# MagEnc2.net
KiCad netlist of a schematic drawn in EAGLE
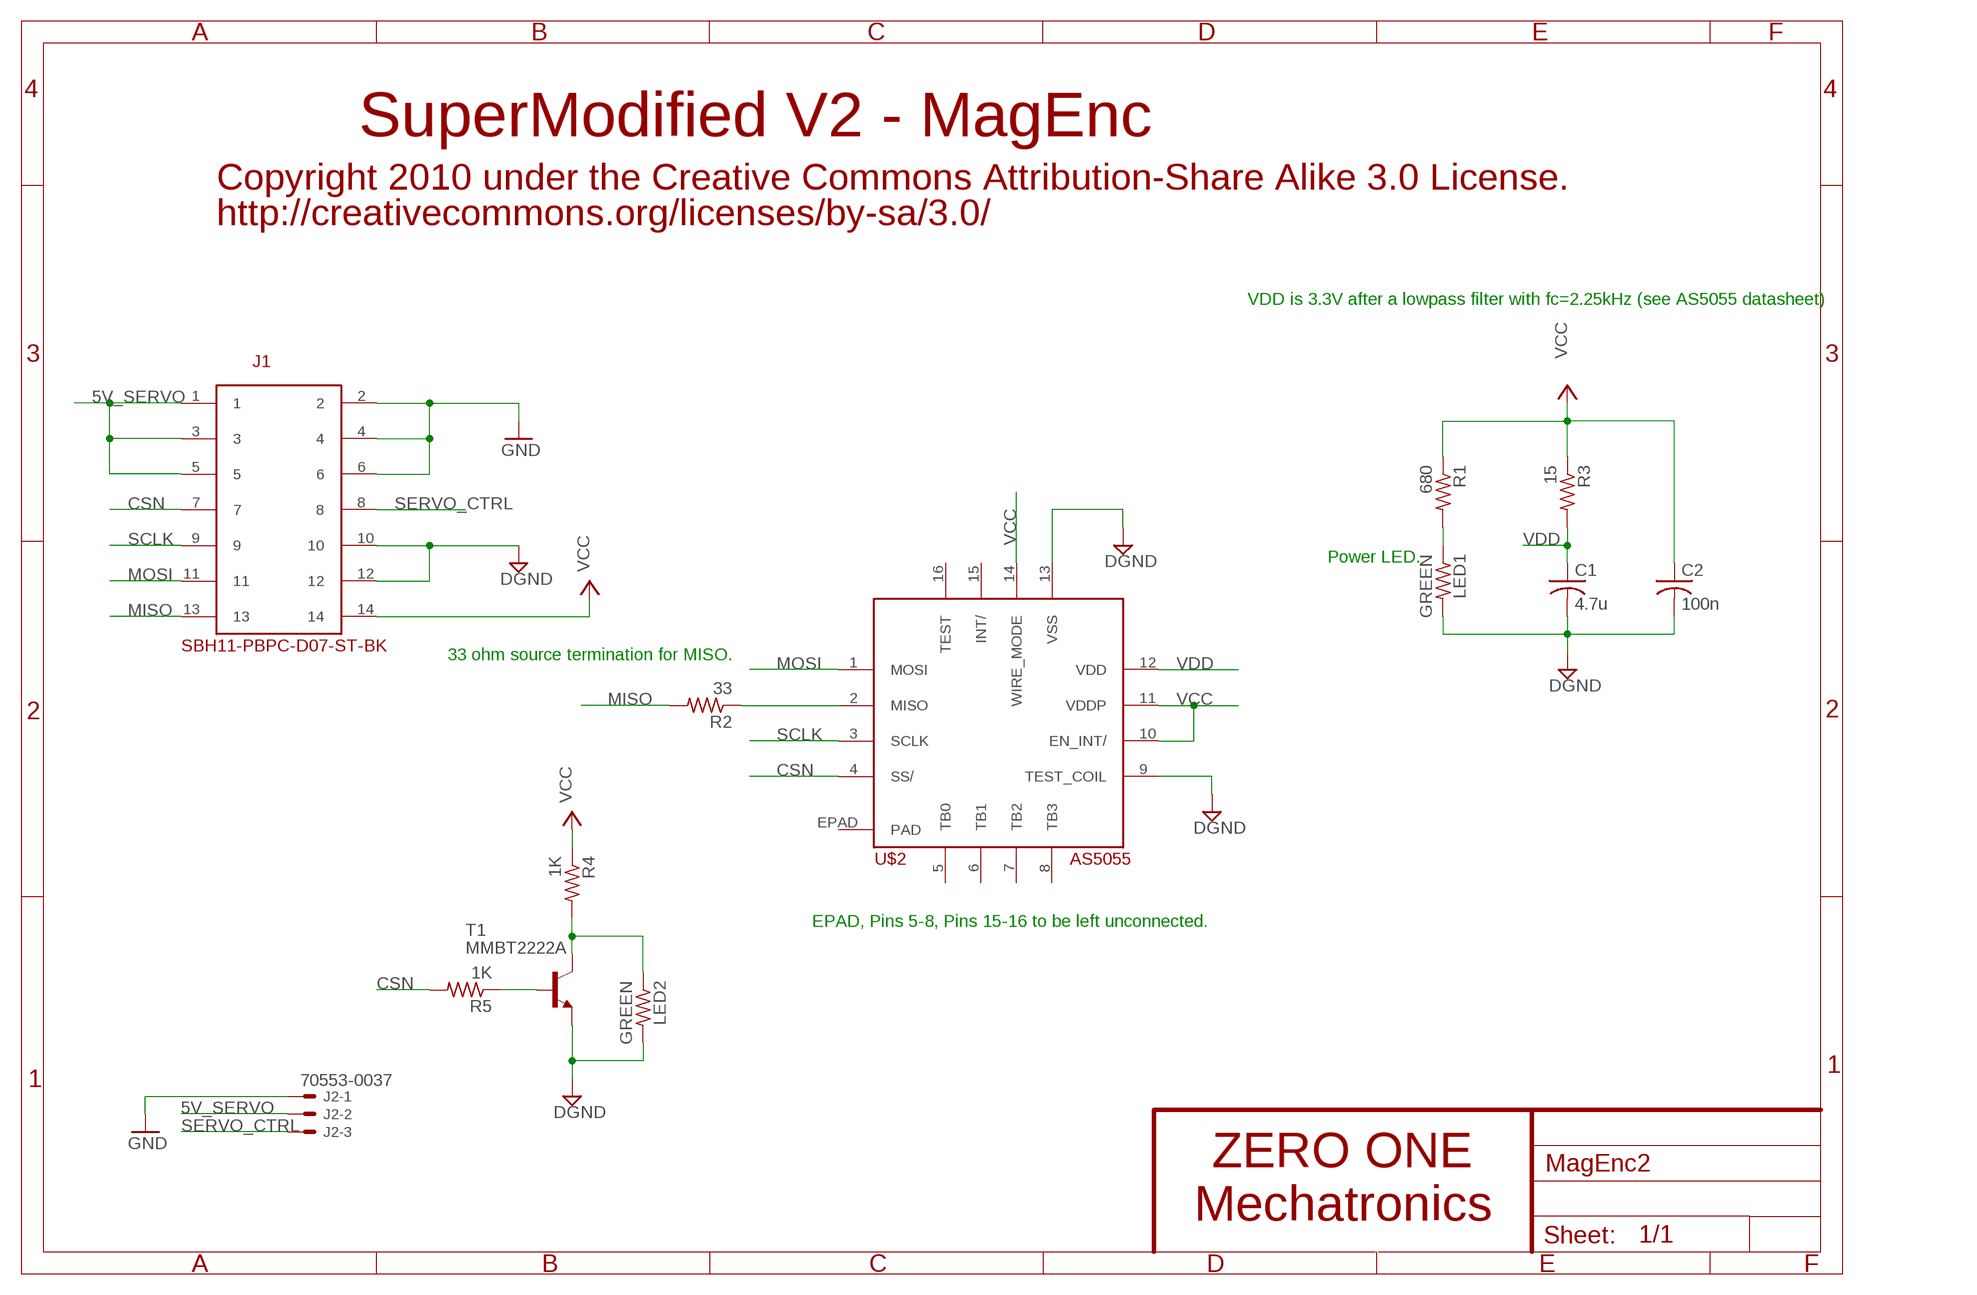
[diagram p0: schematic, sheet 1]

(export (version "E")
  (design (tool "Eeschema 10.0.6"))
  (components
    (comp (ref "C1")
      (value "4.7u")
      (footprint "eagle-import:C0402")
      (libsource (lib "eagle-import") (part "C-USC0402"))
    )
    (comp (ref "C2")
      (value "100n")
      (footprint "eagle-import:C0402")
      (libsource (lib "eagle-import") (part "C-USC0402"))
    )
    (comp (ref "J1")
      (value "SBH11-PBPC-D07-ST-BK")
      (footprint "eagle-import:SBH11-PBPC-D07-ST-BK")
      (libsource (lib "eagle-import") (part "SBH11-PBPC-D07-ST-BK"))
    )
    (comp (ref "J2")
      (value "70553-0037")
      (footprint "eagle-import:70553-03")
      (libsource (lib "eagle-import") (part "C-GRID-03-70553"))
    )
    (comp (ref "LED1")
      (value "GREEN")
      (footprint "eagle-import:R0402")
      (libsource (lib "eagle-import") (part "R-US_R0402"))
    )
    (comp (ref "LED2")
      (value "GREEN")
      (footprint "eagle-import:R0402")
      (libsource (lib "eagle-import") (part "R-US_R0402"))
    )
    (comp (ref "R1")
      (value "680")
      (footprint "eagle-import:R0402")
      (libsource (lib "eagle-import") (part "R-US_R0402"))
    )
    (comp (ref "R2")
      (value "33")
      (footprint "eagle-import:R0402")
      (libsource (lib "eagle-import") (part "R-US_R0402"))
    )
    (comp (ref "R3")
      (value "15")
      (footprint "eagle-import:R0402")
      (libsource (lib "eagle-import") (part "R-US_R0402"))
    )
    (comp (ref "R4")
      (value "1K")
      (footprint "eagle-import:R0402")
      (libsource (lib "eagle-import") (part "R-US_R0402"))
    )
    (comp (ref "R5")
      (value "1K")
      (footprint "eagle-import:R0402")
      (libsource (lib "eagle-import") (part "R-US_R0402"))
    )
    (comp (ref "T1")
      (value "MMBT2222A")
      (footprint "eagle-import:SOT23-BEC")
      (libsource (lib "eagle-import") (part "-NPN-SOT23-BECMMBT2222ALT1"))
    )
    (comp (ref "U$2")
      (value "AS5055")
      (footprint "eagle-import:AS5055")
      (libsource (lib "eagle-import") (part "AS5055"))
    )
  )
  (nets
    (net (code "1") (name "/5V_SERVO") (class "Default")
      (node (ref "J1") (pin "1") (pinfunction "1_1") (pintype "bidirectional"))
      (node (ref "J1") (pin "3") (pinfunction "3_3") (pintype "bidirectional"))
      (node (ref "J1") (pin "5") (pinfunction "5_5") (pintype "bidirectional"))
      (node (ref "J2") (pin "2") (pinfunction "S_2") (pintype "passive"))
    )
    (net (code "2") (name "/CSN") (class "Default")
      (node (ref "J1") (pin "7") (pinfunction "7_7") (pintype "bidirectional"))
      (node (ref "R5") (pin "2") (pinfunction "2_2") (pintype "passive"))
      (node (ref "U$2") (pin "4") (pinfunction "SS/_4") (pintype "bidirectional"))
    )
    (net (code "3") (name "/MISO") (class "Default")
      (node (ref "J1") (pin "13") (pinfunction "13_13") (pintype "bidirectional"))
      (node (ref "R2") (pin "2") (pinfunction "2_2") (pintype "passive"))
    )
    (net (code "4") (name "/MOSI") (class "Default")
      (node (ref "J1") (pin "11") (pinfunction "11_11") (pintype "bidirectional"))
      (node (ref "U$2") (pin "1") (pinfunction "MOSI_1") (pintype "bidirectional"))
    )
    (net (code "5") (name "/SCLK") (class "Default")
      (node (ref "J1") (pin "9") (pinfunction "9_9") (pintype "bidirectional"))
      (node (ref "U$2") (pin "3") (pinfunction "SCLK_3") (pintype "bidirectional"))
    )
    (net (code "6") (name "/SERVO_CTRL") (class "Default")
      (node (ref "J1") (pin "8") (pinfunction "8_8") (pintype "bidirectional"))
      (node (ref "J2") (pin "3") (pinfunction "S_3") (pintype "passive"))
    )
    (net (code "7") (name "/VDD") (class "Default")
      (node (ref "C1") (pin "1") (pinfunction "1_1") (pintype "passive"))
      (node (ref "R3") (pin "2") (pinfunction "2_2") (pintype "passive"))
      (node (ref "U$2") (pin "12") (pinfunction "VDD_12") (pintype "bidirectional"))
    )
    (net (code "8") (name "DGND") (class "Default")
      (node (ref "C1") (pin "2") (pinfunction "2_2") (pintype "passive"))
      (node (ref "C2") (pin "2") (pinfunction "2_2") (pintype "passive"))
      (node (ref "J1") (pin "10") (pinfunction "10_10") (pintype "bidirectional"))
      (node (ref "J1") (pin "12") (pinfunction "12_12") (pintype "bidirectional"))
      (node (ref "LED1") (pin "2") (pinfunction "2_2") (pintype "passive"))
      (node (ref "LED2") (pin "2") (pinfunction "2_2") (pintype "passive"))
      (node (ref "T1") (pin "E") (pinfunction "E_E") (pintype "passive"))
      (node (ref "U$2") (pin "13") (pinfunction "VSS_13") (pintype "bidirectional"))
      (node (ref "U$2") (pin "9") (pinfunction "TEST_COIL_9") (pintype "bidirectional"))
    )
    (net (code "9") (name "GND") (class "Default")
      (node (ref "J1") (pin "2") (pinfunction "2_2") (pintype "bidirectional"))
      (node (ref "J1") (pin "4") (pinfunction "4_4") (pintype "bidirectional"))
      (node (ref "J1") (pin "6") (pinfunction "6_6") (pintype "bidirectional"))
      (node (ref "J2") (pin "1") (pinfunction "S_1") (pintype "passive"))
    )
    (net (code "10") (name "Net-(LED1-Pad1)") (class "Default")
      (node (ref "LED1") (pin "1") (pinfunction "1_1") (pintype "passive"))
      (node (ref "R1") (pin "2") (pinfunction "2_2") (pintype "passive"))
    )
    (net (code "11") (name "Net-(LED2-Pad1)") (class "Default")
      (node (ref "LED2") (pin "1") (pinfunction "1_1") (pintype "passive"))
      (node (ref "R4") (pin "2") (pinfunction "2_2") (pintype "passive"))
      (node (ref "T1") (pin "C") (pinfunction "C_C") (pintype "passive"))
    )
    (net (code "12") (name "Net-(R5-Pad1)") (class "Default")
      (node (ref "R5") (pin "1") (pinfunction "1_1") (pintype "passive"))
      (node (ref "T1") (pin "B") (pinfunction "B_B") (pintype "passive"))
    )
    (net (code "13") (name "Net-(U$2-MISO)") (class "Default")
      (node (ref "R2") (pin "1") (pinfunction "1_1") (pintype "passive"))
      (node (ref "U$2") (pin "2") (pinfunction "MISO_2") (pintype "bidirectional"))
    )
    (net (code "14") (name "VCC") (class "Default")
      (node (ref "C2") (pin "1") (pinfunction "1_1") (pintype "passive"))
      (node (ref "J1") (pin "14") (pinfunction "14_14") (pintype "bidirectional"))
      (node (ref "R1") (pin "1") (pinfunction "1_1") (pintype "passive"))
      (node (ref "R3") (pin "1") (pinfunction "1_1") (pintype "passive"))
      (node (ref "R4") (pin "1") (pinfunction "1_1") (pintype "passive"))
      (node (ref "U$2") (pin "10") (pinfunction "EN_INT/_10") (pintype "bidirectional"))
      (node (ref "U$2") (pin "11") (pinfunction "VDDP_11") (pintype "bidirectional"))
      (node (ref "U$2") (pin "14") (pinfunction "WIRE_MODE_14") (pintype "bidirectional"))
    )
    (net (code "15") (name "unconnected-(U$2-INT{slash}-Pad15)") (class "Default")
      (node (ref "U$2") (pin "15") (pinfunction "INT/_15") (pintype "bidirectional"))
    )
    (net (code "16") (name "unconnected-(U$2-PAD-PadEPAD)") (class "Default")
      (node (ref "U$2") (pin "EPAD") (pinfunction "PAD_EPAD") (pintype "bidirectional"))
    )
    (net (code "17") (name "unconnected-(U$2-TB0-Pad5)") (class "Default")
      (node (ref "U$2") (pin "5") (pinfunction "TB0_5") (pintype "bidirectional"))
    )
    (net (code "18") (name "unconnected-(U$2-TB1-Pad6)") (class "Default")
      (node (ref "U$2") (pin "6") (pinfunction "TB1_6") (pintype "bidirectional"))
    )
    (net (code "19") (name "unconnected-(U$2-TB2-Pad7)") (class "Default")
      (node (ref "U$2") (pin "7") (pinfunction "TB2_7") (pintype "bidirectional"))
    )
    (net (code "20") (name "unconnected-(U$2-TB3-Pad8)") (class "Default")
      (node (ref "U$2") (pin "8") (pinfunction "TB3_8") (pintype "bidirectional"))
    )
    (net (code "21") (name "unconnected-(U$2-TEST-Pad16)") (class "Default")
      (node (ref "U$2") (pin "16") (pinfunction "TEST_16") (pintype "bidirectional"))
    )
  )
)
